# Aquaduino_mega32_u4_v1_5.net
KiCad netlist of a schematic drawn in EAGLE
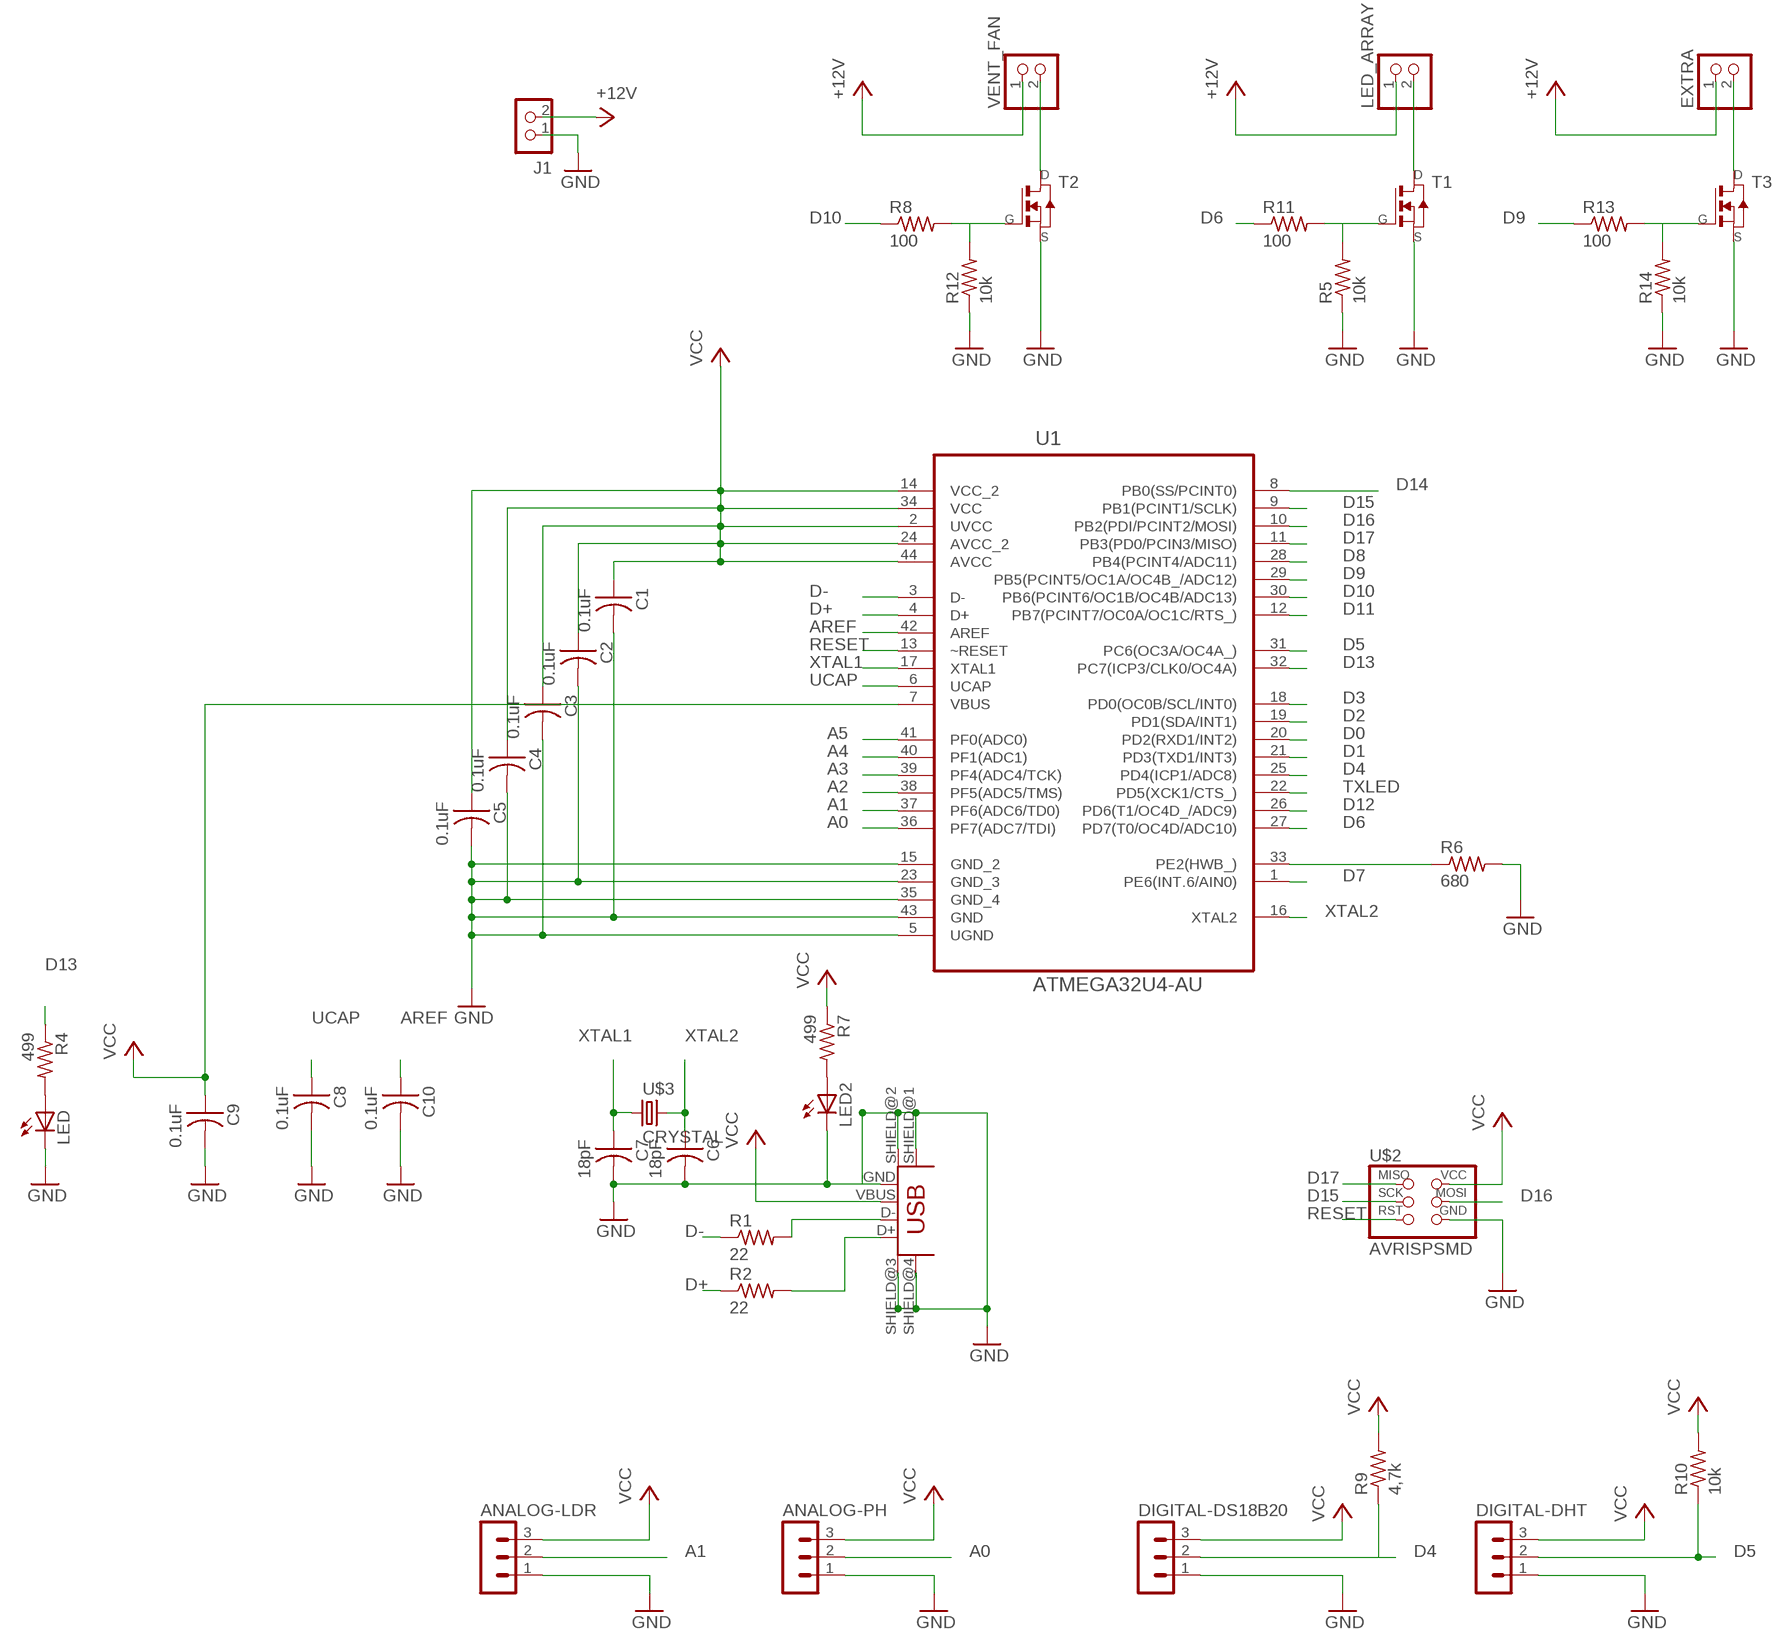
[diagram p0: schematic, sheet 1]

(export (version "E")
  (design (tool "Eeschema 10.0.6"))
  (components
    (comp (ref "ANALOG-LDR")
      (value "MA03-1")
      (footprint "eagle-import:MA03-1")
      (libsource (lib "eagle-import") (part "MA03-1"))
    )
    (comp (ref "ANALOG-PH")
      (value "MA03-1")
      (footprint "eagle-import:MA03-1")
      (libsource (lib "eagle-import") (part "MA03-1"))
    )
    (comp (ref "C1")
      (value "0.1uF")
      (footprint "eagle-import:C1206FAB")
      (libsource (lib "eagle-import") (part "CAP-US1206FAB"))
    )
    (comp (ref "C2")
      (value "0.1uF")
      (footprint "eagle-import:C1206FAB")
      (libsource (lib "eagle-import") (part "CAP-US1206FAB"))
    )
    (comp (ref "C3")
      (value "0.1uF")
      (footprint "eagle-import:C1206FAB")
      (libsource (lib "eagle-import") (part "CAP-US1206FAB"))
    )
    (comp (ref "C4")
      (value "0.1uF")
      (footprint "eagle-import:C1206FAB")
      (libsource (lib "eagle-import") (part "CAP-US1206FAB"))
    )
    (comp (ref "C5")
      (value "0.1uF")
      (footprint "eagle-import:C1206FAB")
      (libsource (lib "eagle-import") (part "CAP-US1206FAB"))
    )
    (comp (ref "C6")
      (value "18pF")
      (footprint "eagle-import:C1206FAB")
      (libsource (lib "eagle-import") (part "CAP-US1206FAB"))
    )
    (comp (ref "C7")
      (value "18pF")
      (footprint "eagle-import:C1206FAB")
      (libsource (lib "eagle-import") (part "CAP-US1206FAB"))
    )
    (comp (ref "C8")
      (value "0.1uF")
      (footprint "eagle-import:C1206FAB")
      (libsource (lib "eagle-import") (part "CAP-US1206FAB"))
    )
    (comp (ref "C9")
      (value "0.1uF")
      (footprint "eagle-import:C1206FAB")
      (libsource (lib "eagle-import") (part "CAP-US1206FAB"))
    )
    (comp (ref "C10")
      (value "0.1uF")
      (footprint "eagle-import:C1206FAB")
      (libsource (lib "eagle-import") (part "CAP-US1206FAB"))
    )
    (comp (ref "DIGITAL-DHT")
      (value "MA03-1")
      (footprint "eagle-import:MA03-1")
      (libsource (lib "eagle-import") (part "MA03-1"))
    )
    (comp (ref "DIGITAL-DS18B20")
      (value "MA03-1")
      (footprint "eagle-import:MA03-1")
      (libsource (lib "eagle-import") (part "MA03-1"))
    )
    (comp (ref "EXTRA")
      (value "PINHD-1X2")
      (footprint "eagle-import:1X02")
      (libsource (lib "eagle-import") (part "PINHD-1X2"))
    )
    (comp (ref "J1")
      (value "CON_TERMINAL_BLOCK_02-5MM")
      (footprint "eagle-import:TERMINAL_BLOCK_2P_5")
      (libsource (lib "eagle-import") (part "CON_TERMINAL_BLOCK_02-5MM"))
    )
    (comp (ref "LED")
      (value "LED1206")
      (footprint "eagle-import:1206")
      (libsource (lib "eagle-import") (part "LED1206"))
    )
    (comp (ref "LED2")
      (value "LED1206")
      (footprint "eagle-import:1206")
      (libsource (lib "eagle-import") (part "LED1206"))
    )
    (comp (ref "LED_ARRAY")
      (value "PINHD-1X2")
      (footprint "eagle-import:1X02")
      (libsource (lib "eagle-import") (part "PINHD-1X2"))
    )
    (comp (ref "R1")
      (value "22")
      (footprint "eagle-import:R1206FAB")
      (libsource (lib "eagle-import") (part "RES-US1206FAB"))
    )
    (comp (ref "R2")
      (value "22")
      (footprint "eagle-import:R1206FAB")
      (libsource (lib "eagle-import") (part "RES-US1206FAB"))
    )
    (comp (ref "R4")
      (value "499")
      (footprint "eagle-import:1206")
      (libsource (lib "eagle-import") (part "RESISTOR1206"))
    )
    (comp (ref "R5")
      (value "10k")
      (footprint "eagle-import:R1206FAB")
      (libsource (lib "eagle-import") (part "RES-US1206FAB"))
    )
    (comp (ref "R6")
      (value "680")
      (footprint "eagle-import:R1206FAB")
      (libsource (lib "eagle-import") (part "RES-US1206FAB"))
    )
    (comp (ref "R7")
      (value "499")
      (footprint "eagle-import:1206")
      (libsource (lib "eagle-import") (part "RESISTOR1206"))
    )
    (comp (ref "R8")
      (value "100")
      (footprint "eagle-import:R1206FAB")
      (libsource (lib "eagle-import") (part "RES-US1206FAB"))
    )
    (comp (ref "R9")
      (value "4,7k")
      (footprint "eagle-import:R1206FAB")
      (libsource (lib "eagle-import") (part "RES-US1206FAB"))
    )
    (comp (ref "R10")
      (value "10k")
      (footprint "eagle-import:R1206FAB")
      (libsource (lib "eagle-import") (part "RES-US1206FAB"))
    )
    (comp (ref "R11")
      (value "100")
      (footprint "eagle-import:R1206FAB")
      (libsource (lib "eagle-import") (part "RES-US1206FAB"))
    )
    (comp (ref "R12")
      (value "10k")
      (footprint "eagle-import:R1206FAB")
      (libsource (lib "eagle-import") (part "RES-US1206FAB"))
    )
    (comp (ref "R13")
      (value "100")
      (footprint "eagle-import:R1206FAB")
      (libsource (lib "eagle-import") (part "RES-US1206FAB"))
    )
    (comp (ref "R14")
      (value "10k")
      (footprint "eagle-import:R1206FAB")
      (libsource (lib "eagle-import") (part "RES-US1206FAB"))
    )
    (comp (ref "T1")
      (value "NMOSFETTO252")
      (footprint "eagle-import:TO252")
      (libsource (lib "eagle-import") (part "NMOSFETTO252"))
    )
    (comp (ref "T2")
      (value "NMOSFETTO252")
      (footprint "eagle-import:TO252")
      (libsource (lib "eagle-import") (part "NMOSFETTO252"))
    )
    (comp (ref "T3")
      (value "NMOSFETTO252")
      (footprint "eagle-import:TO252")
      (libsource (lib "eagle-import") (part "NMOSFETTO252"))
    )
    (comp (ref "U$1")
      (value "USB_MINIB")
      (footprint "eagle-import:USB_MINIB")
      (libsource (lib "eagle-import") (part "USB_MINIB"))
    )
    (comp (ref "U$2")
      (value "AVRISPSMD")
      (footprint "eagle-import:2X03SMD")
      (libsource (lib "eagle-import") (part "AVRISPSMD"))
    )
    (comp (ref "U$3")
      (value "CRYSTAL")
      (footprint "eagle-import:2-SMD-5X3MM")
      (libsource (lib "eagle-import") (part "CRYSTAL"))
    )
    (comp (ref "U1")
      (value "ATMEGA32U4-AU")
      (footprint "eagle-import:QFP80P1200X1200X120-44N")
      (libsource (lib "eagle-import") (part "ATMEGA32U4-AU"))
    )
    (comp (ref "VENT_FAN")
      (value "PINHD-1X2")
      (footprint "eagle-import:1X02")
      (libsource (lib "eagle-import") (part "PINHD-1X2"))
    )
  )
  (nets
    (net (code "1") (name "+12V") (class "Default")
      (node (ref "ANALOG-LDR") (pin "3") (pinfunction "3_3") (pintype "passive"))
      (node (ref "ANALOG-PH") (pin "3") (pinfunction "3_3") (pintype "passive"))
      (node (ref "C1") (pin "1") (pinfunction "1_1") (pintype "passive"))
      (node (ref "C2") (pin "1") (pinfunction "1_1") (pintype "passive"))
      (node (ref "C3") (pin "1") (pinfunction "1_1") (pintype "passive"))
      (node (ref "C4") (pin "1") (pinfunction "1_1") (pintype "passive"))
      (node (ref "C5") (pin "1") (pinfunction "1_1") (pintype "passive"))
      (node (ref "C9") (pin "1") (pinfunction "1_1") (pintype "passive"))
      (node (ref "DIGITAL-DHT") (pin "3") (pinfunction "3_3") (pintype "passive"))
      (node (ref "DIGITAL-DS18B20") (pin "3") (pinfunction "3_3") (pintype "passive"))
      (node (ref "EXTRA") (pin "1") (pinfunction "1_1") (pintype "passive"))
      (node (ref "J1") (pin "2") (pinfunction "2_2") (pintype "passive"))
      (node (ref "LED_ARRAY") (pin "1") (pinfunction "1_1") (pintype "passive"))
      (node (ref "R10") (pin "2") (pinfunction "2_2") (pintype "passive"))
      (node (ref "R7") (pin "1") (pinfunction "1_1") (pintype "passive"))
      (node (ref "R9") (pin "2") (pinfunction "2_2") (pintype "passive"))
      (node (ref "U$1") (pin "VBUS") (pinfunction "VBUS_VBUS") (pintype "bidirectional"))
      (node (ref "U$2") (pin "2") (pinfunction "VCC_2") (pintype "passive"))
      (node (ref "U1") (pin "14") (pinfunction "VCC_2_14") (pintype "power_in"))
      (node (ref "U1") (pin "2") (pinfunction "UVCC_2") (pintype "power_in"))
      (node (ref "U1") (pin "24") (pinfunction "AVCC_2_24") (pintype "power_in"))
      (node (ref "U1") (pin "34") (pinfunction "VCC_34") (pintype "power_in"))
      (node (ref "U1") (pin "44") (pinfunction "AVCC_44") (pintype "power_in"))
      (node (ref "U1") (pin "7") (pinfunction "VBUS_7") (pintype "input"))
      (node (ref "VENT_FAN") (pin "1") (pinfunction "1_1") (pintype "passive"))
    )
    (net (code "2") (name "/A0") (class "Default")
      (node (ref "ANALOG-PH") (pin "2") (pinfunction "2_2") (pintype "passive"))
      (node (ref "U1") (pin "36") (pinfunction "PF7(ADC7/TDI)_36") (pintype "bidirectional"))
    )
    (net (code "3") (name "/A1") (class "Default")
      (node (ref "ANALOG-LDR") (pin "2") (pinfunction "2_2") (pintype "passive"))
      (node (ref "U1") (pin "37") (pinfunction "PF6(ADC6/TD0)_37") (pintype "bidirectional"))
    )
    (net (code "4") (name "/A2") (class "Default")
      (node (ref "U1") (pin "38") (pinfunction "PF5(ADC5/TMS)_38") (pintype "bidirectional"))
    )
    (net (code "5") (name "/A3") (class "Default")
      (node (ref "U1") (pin "39") (pinfunction "PF4(ADC4/TCK)_39") (pintype "bidirectional"))
    )
    (net (code "6") (name "/A4") (class "Default")
      (node (ref "U1") (pin "40") (pinfunction "PF1(ADC1)_40") (pintype "bidirectional"))
    )
    (net (code "7") (name "/A5") (class "Default")
      (node (ref "U1") (pin "41") (pinfunction "PF0(ADC0)_41") (pintype "bidirectional"))
    )
    (net (code "8") (name "/AREF") (class "Default")
      (node (ref "C10") (pin "1") (pinfunction "1_1") (pintype "passive"))
      (node (ref "U1") (pin "42") (pinfunction "AREF_42") (pintype "input"))
    )
    (net (code "9") (name "/D+") (class "Default")
      (node (ref "R2") (pin "1") (pinfunction "1_1") (pintype "passive"))
      (node (ref "U1") (pin "4") (pinfunction "D+_4") (pintype "passive"))
    )
    (net (code "10") (name "/D-") (class "Default")
      (node (ref "R1") (pin "1") (pinfunction "1_1") (pintype "passive"))
      (node (ref "U1") (pin "3") (pinfunction "D-_3") (pintype "passive"))
    )
    (net (code "11") (name "/D0") (class "Default")
      (node (ref "U1") (pin "20") (pinfunction "PD2(RXD1/INT2)_20") (pintype "bidirectional"))
    )
    (net (code "12") (name "/D1") (class "Default")
      (node (ref "U1") (pin "21") (pinfunction "PD3(TXD1/INT3)_21") (pintype "bidirectional"))
    )
    (net (code "13") (name "/D2") (class "Default")
      (node (ref "U1") (pin "19") (pinfunction "PD1(SDA/INT1)_19") (pintype "bidirectional"))
    )
    (net (code "14") (name "/D3") (class "Default")
      (node (ref "U1") (pin "18") (pinfunction "PD0(OC0B/SCL/INT0)_18") (pintype "bidirectional"))
    )
    (net (code "15") (name "/D4") (class "Default")
      (node (ref "DIGITAL-DS18B20") (pin "2") (pinfunction "2_2") (pintype "passive"))
      (node (ref "R9") (pin "1") (pinfunction "1_1") (pintype "passive"))
      (node (ref "U1") (pin "25") (pinfunction "PD4(ICP1/ADC8)_25") (pintype "bidirectional"))
    )
    (net (code "16") (name "/D5") (class "Default")
      (node (ref "DIGITAL-DHT") (pin "2") (pinfunction "2_2") (pintype "passive"))
      (node (ref "R10") (pin "1") (pinfunction "1_1") (pintype "passive"))
      (node (ref "U1") (pin "31") (pinfunction "PC6(OC3A/OC4A_)_31") (pintype "bidirectional"))
    )
    (net (code "17") (name "/D6") (class "Default")
      (node (ref "R11") (pin "1") (pinfunction "1_1") (pintype "passive"))
      (node (ref "U1") (pin "27") (pinfunction "PD7(T0/OC4D/ADC10)_27") (pintype "bidirectional"))
    )
    (net (code "18") (name "/D7") (class "Default")
      (node (ref "U1") (pin "1") (pinfunction "PE6(INT.6/AIN0)_1") (pintype "bidirectional"))
    )
    (net (code "19") (name "/D8") (class "Default")
      (node (ref "U1") (pin "28") (pinfunction "PB4(PCINT4/ADC11)_28") (pintype "bidirectional"))
    )
    (net (code "20") (name "/D9") (class "Default")
      (node (ref "R13") (pin "1") (pinfunction "1_1") (pintype "passive"))
      (node (ref "U1") (pin "29") (pinfunction "PB5(PCINT5/OC1A/OC4B_/ADC12)_29") (pintype "bidirectional"))
    )
    (net (code "21") (name "/D10") (class "Default")
      (node (ref "R8") (pin "1") (pinfunction "1_1") (pintype "passive"))
      (node (ref "U1") (pin "30") (pinfunction "PB6(PCINT6/OC1B/OC4B/ADC13)_30") (pintype "bidirectional"))
    )
    (net (code "22") (name "/D11") (class "Default")
      (node (ref "U1") (pin "12") (pinfunction "PB7(PCINT7/OC0A/OC1C/RTS_)_12") (pintype "bidirectional"))
    )
    (net (code "23") (name "/D12") (class "Default")
      (node (ref "U1") (pin "26") (pinfunction "PD6(T1/OC4D_/ADC9)_26") (pintype "bidirectional"))
    )
    (net (code "24") (name "/D13") (class "Default")
      (node (ref "R4") (pin "1") (pinfunction "1_1") (pintype "passive"))
      (node (ref "U1") (pin "32") (pinfunction "PC7(ICP3/CLK0/OC4A)_32") (pintype "bidirectional"))
    )
    (net (code "25") (name "/D14") (class "Default")
      (node (ref "U1") (pin "8") (pinfunction "PB0(SS/PCINT0)_8") (pintype "bidirectional"))
    )
    (net (code "26") (name "/D15") (class "Default")
      (node (ref "U$2") (pin "3") (pinfunction "SCK_3") (pintype "passive"))
      (node (ref "U1") (pin "9") (pinfunction "PB1(PCINT1/SCLK)_9") (pintype "bidirectional"))
    )
    (net (code "27") (name "/D16") (class "Default")
      (node (ref "U$2") (pin "4") (pinfunction "MOSI_4") (pintype "passive"))
      (node (ref "U1") (pin "10") (pinfunction "PB2(PDI/PCINT2/MOSI)_10") (pintype "bidirectional"))
    )
    (net (code "28") (name "/D17") (class "Default")
      (node (ref "U$2") (pin "1") (pinfunction "MISO_1") (pintype "passive"))
      (node (ref "U1") (pin "11") (pinfunction "PB3(PD0/PCIN3/MISO)_11") (pintype "bidirectional"))
    )
    (net (code "29") (name "/RESET") (class "Default")
      (node (ref "U$2") (pin "5") (pinfunction "RST_5") (pintype "passive"))
      (node (ref "U1") (pin "13") (pinfunction "~{RESET}_13") (pintype "input"))
    )
    (net (code "30") (name "/TXLED") (class "Default")
      (node (ref "U1") (pin "22") (pinfunction "PD5(XCK1/CTS_)_22") (pintype "bidirectional"))
    )
    (net (code "31") (name "/UCAP") (class "Default")
      (node (ref "C8") (pin "1") (pinfunction "1_1") (pintype "passive"))
      (node (ref "U1") (pin "6") (pinfunction "UCAP_6") (pintype "power_in"))
    )
    (net (code "32") (name "/XTAL1") (class "Default")
      (node (ref "C7") (pin "1") (pinfunction "1_1") (pintype "passive"))
      (node (ref "U$3") (pin "P$1") (pinfunction "1_P$1") (pintype "passive"))
      (node (ref "U1") (pin "17") (pinfunction "XTAL1_17") (pintype "input"))
    )
    (net (code "33") (name "/XTAL2") (class "Default")
      (node (ref "C6") (pin "1") (pinfunction "1_1") (pintype "passive"))
      (node (ref "U$3") (pin "P$2") (pinfunction "2_P$2") (pintype "passive"))
      (node (ref "U1") (pin "16") (pinfunction "XTAL2_16") (pintype "output"))
    )
    (net (code "34") (name "GND") (class "Default")
      (node (ref "ANALOG-LDR") (pin "1") (pinfunction "1_1") (pintype "passive"))
      (node (ref "ANALOG-PH") (pin "1") (pinfunction "1_1") (pintype "passive"))
      (node (ref "C1") (pin "2") (pinfunction "2_2") (pintype "passive"))
      (node (ref "C10") (pin "2") (pinfunction "2_2") (pintype "passive"))
      (node (ref "C2") (pin "2") (pinfunction "2_2") (pintype "passive"))
      (node (ref "C3") (pin "2") (pinfunction "2_2") (pintype "passive"))
      (node (ref "C4") (pin "2") (pinfunction "2_2") (pintype "passive"))
      (node (ref "C5") (pin "2") (pinfunction "2_2") (pintype "passive"))
      (node (ref "C6") (pin "2") (pinfunction "2_2") (pintype "passive"))
      (node (ref "C7") (pin "2") (pinfunction "2_2") (pintype "passive"))
      (node (ref "C8") (pin "2") (pinfunction "2_2") (pintype "passive"))
      (node (ref "C9") (pin "2") (pinfunction "2_2") (pintype "passive"))
      (node (ref "DIGITAL-DHT") (pin "1") (pinfunction "1_1") (pintype "passive"))
      (node (ref "DIGITAL-DS18B20") (pin "1") (pinfunction "1_1") (pintype "passive"))
      (node (ref "J1") (pin "1") (pinfunction "1_1") (pintype "passive"))
      (node (ref "LED") (pin "2") (pinfunction "C_2") (pintype "passive"))
      (node (ref "LED2") (pin "2") (pinfunction "C_2") (pintype "passive"))
      (node (ref "R12") (pin "1") (pinfunction "1_1") (pintype "passive"))
      (node (ref "R14") (pin "1") (pinfunction "1_1") (pintype "passive"))
      (node (ref "R5") (pin "1") (pinfunction "1_1") (pintype "passive"))
      (node (ref "R6") (pin "2") (pinfunction "2_2") (pintype "passive"))
      (node (ref "T1") (pin "2") (pinfunction "S_2") (pintype "passive"))
      (node (ref "T2") (pin "2") (pinfunction "S_2") (pintype "passive"))
      (node (ref "T3") (pin "2") (pinfunction "S_2") (pintype "passive"))
      (node (ref "U$1") (pin "GND") (pinfunction "GND_GND") (pintype "bidirectional"))
      (node (ref "U$1") (pin "SHIELD@1") (pinfunction "SHIELD_SHIELD@1") (pintype "passive"))
      (node (ref "U$1") (pin "SHIELD@2") (pinfunction "SHIELD1_SHIELD@2") (pintype "passive"))
      (node (ref "U$1") (pin "SHIELD@3") (pinfunction "SHIELD2_SHIELD@3") (pintype "passive"))
      (node (ref "U$1") (pin "SHIELD@4") (pinfunction "SHIELD3_SHIELD@4") (pintype "passive"))
      (node (ref "U$2") (pin "6") (pinfunction "GND_6") (pintype "passive"))
      (node (ref "U1") (pin "15") (pinfunction "GND_2_15") (pintype "passive"))
      (node (ref "U1") (pin "23") (pinfunction "GND_3_23") (pintype "passive"))
      (node (ref "U1") (pin "35") (pinfunction "GND_4_35") (pintype "passive"))
      (node (ref "U1") (pin "43") (pinfunction "GND_43") (pintype "passive"))
      (node (ref "U1") (pin "5") (pinfunction "UGND_5") (pintype "passive"))
    )
    (net (code "35") (name "Net-(LED-A)") (class "Default")
      (node (ref "LED") (pin "1") (pinfunction "A_1") (pintype "passive"))
      (node (ref "R4") (pin "2") (pinfunction "2_2") (pintype "passive"))
    )
    (net (code "36") (name "Net-(LED2-A)") (class "Default")
      (node (ref "LED2") (pin "1") (pinfunction "A_1") (pintype "passive"))
      (node (ref "R7") (pin "2") (pinfunction "2_2") (pintype "passive"))
    )
    (net (code "37") (name "Net-(R1-Pad2)") (class "Default")
      (node (ref "R1") (pin "2") (pinfunction "2_2") (pintype "passive"))
      (node (ref "U$1") (pin "D-") (pinfunction "D-_D-") (pintype "bidirectional"))
    )
    (net (code "38") (name "Net-(R2-Pad2)") (class "Default")
      (node (ref "R2") (pin "2") (pinfunction "2_2") (pintype "passive"))
      (node (ref "U$1") (pin "D+") (pinfunction "D+_D+") (pintype "bidirectional"))
    )
    (net (code "39") (name "Net-(T1-D)") (class "Default")
      (node (ref "LED_ARRAY") (pin "2") (pinfunction "2_2") (pintype "passive"))
      (node (ref "T1") (pin "3") (pinfunction "D_3") (pintype "passive"))
    )
    (net (code "40") (name "Net-(T1-G)") (class "Default")
      (node (ref "R11") (pin "2") (pinfunction "2_2") (pintype "passive"))
      (node (ref "R5") (pin "2") (pinfunction "2_2") (pintype "passive"))
      (node (ref "T1") (pin "1") (pinfunction "G_1") (pintype "passive"))
    )
    (net (code "41") (name "Net-(T2-D)") (class "Default")
      (node (ref "T2") (pin "3") (pinfunction "D_3") (pintype "passive"))
      (node (ref "VENT_FAN") (pin "2") (pinfunction "2_2") (pintype "passive"))
    )
    (net (code "42") (name "Net-(T2-G)") (class "Default")
      (node (ref "R12") (pin "2") (pinfunction "2_2") (pintype "passive"))
      (node (ref "R8") (pin "2") (pinfunction "2_2") (pintype "passive"))
      (node (ref "T2") (pin "1") (pinfunction "G_1") (pintype "passive"))
    )
    (net (code "43") (name "Net-(T3-D)") (class "Default")
      (node (ref "EXTRA") (pin "2") (pinfunction "2_2") (pintype "passive"))
      (node (ref "T3") (pin "3") (pinfunction "D_3") (pintype "passive"))
    )
    (net (code "44") (name "Net-(T3-G)") (class "Default")
      (node (ref "R13") (pin "2") (pinfunction "2_2") (pintype "passive"))
      (node (ref "R14") (pin "2") (pinfunction "2_2") (pintype "passive"))
      (node (ref "T3") (pin "1") (pinfunction "G_1") (pintype "passive"))
    )
    (net (code "45") (name "Net-(U1-PE2(HWB_))") (class "Default")
      (node (ref "R6") (pin "1") (pinfunction "1_1") (pintype "passive"))
      (node (ref "U1") (pin "33") (pinfunction "PE2(HWB_)_33") (pintype "bidirectional"))
    )
  )
)
